# RF_pwr_v2.net
KiCad netlist of a schematic drawn in Altium Designer
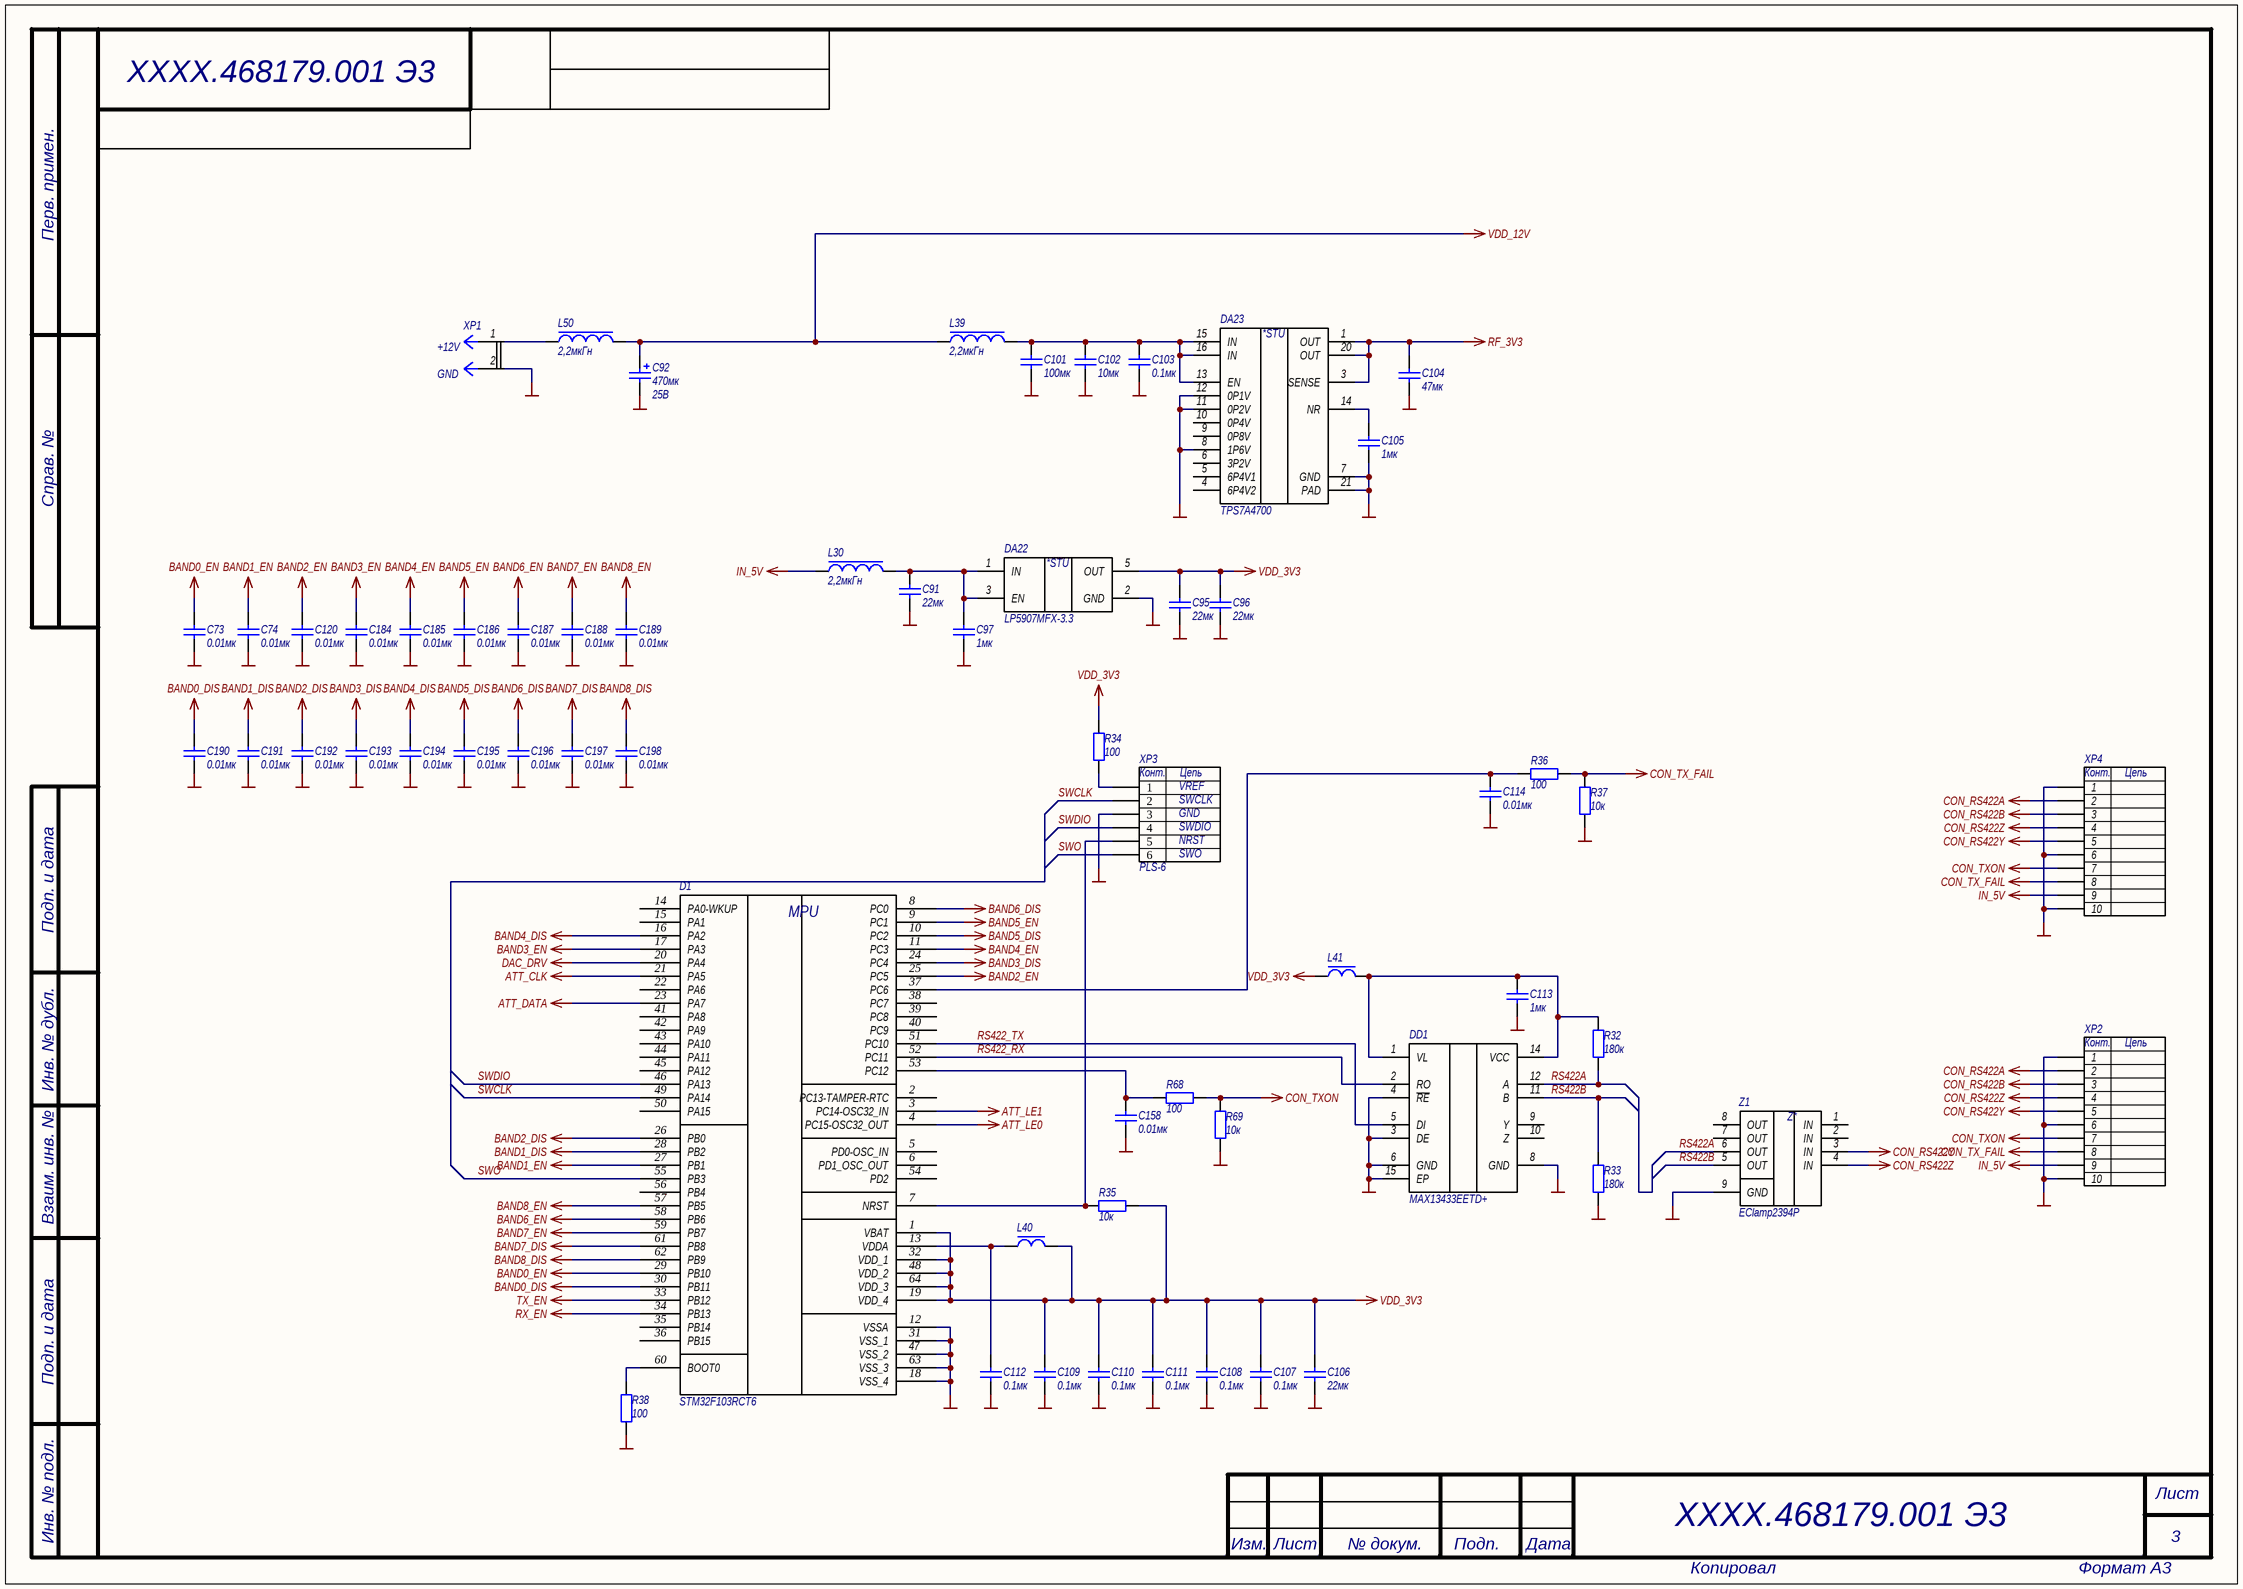
[diagram p0: RF_pwr_v2.SchDoc]

(export (version "E")
  (design (tool "Eeschema 10.0.6"))
  (components
    (comp (ref "C73")
      (value "0.01мк")
      (footprint "CAPC1005X06N")
      (description "Кер. ЧИП-конденсатор")
      (fields (field (name "TOLERANCE") "±20%"))
      (libsource (lib "nels_caps") (part "Кер.ЧИП конд. 0402 0.01мкФ X7R 10%, 50В"))
    )
    (comp (ref "C74")
      (value "0.01мк")
      (footprint "CAPC1005X06N")
      (description "Кер. ЧИП-конденсатор")
      (fields (field (name "TOLERANCE") "±20%"))
      (libsource (lib "nels_caps") (part "Кер.ЧИП конд. 0402 0.01мкФ X7R 10%, 50В"))
    )
    (comp (ref "C91")
      (value "22мк")
      (footprint "CAPC2012X12L")
      (description "Кер. ЧИП-конденсатор")
      (fields (field (name "MANUFACTURER") "TDK") (field (name "TOLERANCE") "±10%"))
      (libsource (lib "nels_caps") (part "Кер.ЧИП конд. 0805 22мкФ X5R 10% 16В"))
    )
    (comp (ref "C92")
      (value "470мк")
      (footprint "CAPAE116103X105N")
      (description "Гибридный ЧИП-конденсатор")
      (fields
        (field (name "TOLERANCE") "±20%")
        (field (name "MANUFACTURERPARTNUMBER") "EEHZK1E471P")
        (field (name "POWER/VOLTAGE") "25В")
        (field (name "PUBLISHER") "Altium Limited")
      )
      (libsource (lib "nels_caps") (part "Конденсатор гибридный SMD 470мкФ ±20% 25В"))
    )
    (comp (ref "C95")
      (value "22мк")
      (footprint "CAPC2012X12L")
      (description "Кер. ЧИП-конденсатор")
      (fields (field (name "MANUFACTURER") "TDK") (field (name "TOLERANCE") "±10%"))
      (libsource (lib "nels_caps") (part "Кер.ЧИП конд. 0805 22мкФ X5R 10% 16В"))
    )
    (comp (ref "C96")
      (value "22мк")
      (footprint "CAPC2012X12L")
      (description "Кер. ЧИП-конденсатор")
      (fields (field (name "MANUFACTURER") "TDK") (field (name "TOLERANCE") "±10%"))
      (libsource (lib "nels_caps") (part "Кер.ЧИП конд. 0805 22мкФ X5R 10% 16В"))
    )
    (comp (ref "C97")
      (value "1мк")
      (footprint "CAPC1005X06N")
      (description "Кер. ЧИП-конденсатор")
      (fields (field (name "TOLERANCE") "±10%"))
      (libsource (lib "nels_caps") (part "Кер.ЧИП конд. 0402 1мкФ X5R 10%, 10В"))
    )
    (comp (ref "C101")
      (value "100мк")
      (footprint "CAPC3216X19L")
      (description "Кер. ЧИП-конденсатор")
      (fields (field (name "MANUFACTURER") "Murata") (field (name "TOLERANCE") "±20%"))
      (libsource (lib "nels_caps") (part "Кер.ЧИП конд. 1206 100мкФ X5R 20% 6.3В"))
    )
    (comp (ref "C102")
      (value "10мк")
      (footprint "CAPC1608X08L")
      (description "Кер. ЧИП-конденсатор")
      (fields (field (name "MANUFACTURER") "Murata") (field (name "TOLERANCE") "±20%"))
      (libsource (lib "nels_caps") (part "Кер.ЧИП конд. 0603 10мкФ X5R 20% 6.3В"))
    )
    (comp (ref "C103")
      (value "0.1мк")
      (footprint "CAPC1005X06N")
      (description "Кер. ЧИП-конденсатор")
      (fields (field (name "TOLERANCE") "±10%"))
      (libsource (lib "nels") (part "Кер.ЧИП конд. 0402 0.1мкФ X7R 10%, 16В"))
    )
    (comp (ref "C104")
      (value "47мк")
      (footprint "CAPC2012X12L")
      (description "Кер. ЧИП-конденсатор")
      (fields (field (name "MANUFACTURER") "Murata") (field (name "TOLERANCE") "±20%"))
      (libsource (lib "nels_caps") (part "Кер.ЧИП конд. 0805 47мкФ X5R 20% 10В"))
    )
    (comp (ref "C105")
      (value "1мк")
      (footprint "CAPC1005X06N")
      (description "Кер. ЧИП-конденсатор")
      (fields (field (name "TOLERANCE") "±10%"))
      (libsource (lib "nels_caps") (part "Кер.ЧИП конд. 0402 1мкФ X5R 10%, 10В"))
    )
    (comp (ref "C106")
      (value "22мк")
      (footprint "CAPC2012X12L")
      (description "Кер. ЧИП-конденсатор")
      (fields (field (name "MANUFACTURER") "TDK") (field (name "TOLERANCE") "±10%"))
      (libsource (lib "nels_caps") (part "Кер.ЧИП конд. 0805 22мкФ X5R 10% 16В"))
    )
    (comp (ref "C107")
      (value "0.1мк")
      (footprint "CAPC1005X06N")
      (description "Кер. ЧИП-конденсатор")
      (fields (field (name "TOLERANCE") "±10%"))
      (libsource (lib "nels") (part "Кер.ЧИП конд. 0402 0.1мкФ X7R 10%, 16В"))
    )
    (comp (ref "C108")
      (value "0.1мк")
      (footprint "CAPC1005X06N")
      (description "Кер. ЧИП-конденсатор")
      (fields (field (name "TOLERANCE") "±10%"))
      (libsource (lib "nels") (part "Кер.ЧИП конд. 0402 0.1мкФ X7R 10%, 16В"))
    )
    (comp (ref "C109")
      (value "0.1мк")
      (footprint "CAPC1005X06N")
      (description "Кер. ЧИП-конденсатор")
      (fields (field (name "TOLERANCE") "±10%"))
      (libsource (lib "nels") (part "Кер.ЧИП конд. 0402 0.1мкФ X7R 10%, 16В"))
    )
    (comp (ref "C110")
      (value "0.1мк")
      (footprint "CAPC1005X06N")
      (description "Кер. ЧИП-конденсатор")
      (fields (field (name "TOLERANCE") "±10%"))
      (libsource (lib "nels") (part "Кер.ЧИП конд. 0402 0.1мкФ X7R 10%, 16В"))
    )
    (comp (ref "C111")
      (value "0.1мк")
      (footprint "CAPC1005X06N")
      (description "Кер. ЧИП-конденсатор")
      (fields (field (name "TOLERANCE") "±10%"))
      (libsource (lib "nels") (part "Кер.ЧИП конд. 0402 0.1мкФ X7R 10%, 16В"))
    )
    (comp (ref "C112")
      (value "0.1мк")
      (footprint "CAPC1005X06N")
      (description "Кер. ЧИП-конденсатор")
      (fields (field (name "TOLERANCE") "±10%"))
      (libsource (lib "nels") (part "Кер.ЧИП конд. 0402 0.1мкФ X7R 10%, 16В"))
    )
    (comp (ref "C113")
      (value "1мк")
      (footprint "CAPC1005X06N")
      (description "Кер. ЧИП-конденсатор")
      (fields (field (name "TOLERANCE") "±10%"))
      (libsource (lib "nels_caps") (part "Кер.ЧИП конд. 0402 1мкФ X5R 10%, 10В"))
    )
    (comp (ref "C114")
      (value "0.01мк")
      (footprint "CAPC1005X06N")
      (description "Кер. ЧИП-конденсатор")
      (fields (field (name "TOLERANCE") "±20%"))
      (libsource (lib "nels_caps") (part "Кер.ЧИП конд. 0402 0.01мкФ X7R 10%, 50В"))
    )
    (comp (ref "C120")
      (value "0.01мк")
      (footprint "CAPC1005X06N")
      (description "Кер. ЧИП-конденсатор")
      (fields (field (name "TOLERANCE") "±20%"))
      (libsource (lib "nels_caps") (part "Кер.ЧИП конд. 0402 0.01мкФ X7R 10%, 50В"))
    )
    (comp (ref "C158")
      (value "0.01мк")
      (footprint "CAPC1005X06N")
      (description "Кер. ЧИП-конденсатор")
      (fields (field (name "TOLERANCE") "±20%"))
      (libsource (lib "nels_caps") (part "Кер.ЧИП конд. 0402 0.01мкФ X7R 10%, 50В"))
    )
    (comp (ref "C184")
      (value "0.01мк")
      (footprint "CAPC1005X06N")
      (description "Кер. ЧИП-конденсатор")
      (fields (field (name "TOLERANCE") "±20%"))
      (libsource (lib "nels_caps") (part "Кер.ЧИП конд. 0402 0.01мкФ X7R 10%, 50В"))
    )
    (comp (ref "C185")
      (value "0.01мк")
      (footprint "CAPC1005X06N")
      (description "Кер. ЧИП-конденсатор")
      (fields (field (name "TOLERANCE") "±20%"))
      (libsource (lib "nels_caps") (part "Кер.ЧИП конд. 0402 0.01мкФ X7R 10%, 50В"))
    )
    (comp (ref "C186")
      (value "0.01мк")
      (footprint "CAPC1005X06N")
      (description "Кер. ЧИП-конденсатор")
      (fields (field (name "TOLERANCE") "±20%"))
      (libsource (lib "nels_caps") (part "Кер.ЧИП конд. 0402 0.01мкФ X7R 10%, 50В"))
    )
    (comp (ref "C187")
      (value "0.01мк")
      (footprint "CAPC1005X06N")
      (description "Кер. ЧИП-конденсатор")
      (fields (field (name "TOLERANCE") "±20%"))
      (libsource (lib "nels_caps") (part "Кер.ЧИП конд. 0402 0.01мкФ X7R 10%, 50В"))
    )
    (comp (ref "C188")
      (value "0.01мк")
      (footprint "CAPC1005X06N")
      (description "Кер. ЧИП-конденсатор")
      (fields (field (name "TOLERANCE") "±20%"))
      (libsource (lib "nels_caps") (part "Кер.ЧИП конд. 0402 0.01мкФ X7R 10%, 50В"))
    )
    (comp (ref "C189")
      (value "0.01мк")
      (footprint "CAPC1005X06N")
      (description "Кер. ЧИП-конденсатор")
      (fields (field (name "TOLERANCE") "±20%"))
      (libsource (lib "nels_caps") (part "Кер.ЧИП конд. 0402 0.01мкФ X7R 10%, 50В"))
    )
    (comp (ref "C190")
      (value "0.01мк")
      (footprint "CAPC1005X06N")
      (description "Кер. ЧИП-конденсатор")
      (fields (field (name "TOLERANCE") "±20%"))
      (libsource (lib "nels_caps") (part "Кер.ЧИП конд. 0402 0.01мкФ X7R 10%, 50В"))
    )
    (comp (ref "C191")
      (value "0.01мк")
      (footprint "CAPC1005X06N")
      (description "Кер. ЧИП-конденсатор")
      (fields (field (name "TOLERANCE") "±20%"))
      (libsource (lib "nels_caps") (part "Кер.ЧИП конд. 0402 0.01мкФ X7R 10%, 50В"))
    )
    (comp (ref "C192")
      (value "0.01мк")
      (footprint "CAPC1005X06N")
      (description "Кер. ЧИП-конденсатор")
      (fields (field (name "TOLERANCE") "±20%"))
      (libsource (lib "nels_caps") (part "Кер.ЧИП конд. 0402 0.01мкФ X7R 10%, 50В"))
    )
    (comp (ref "C193")
      (value "0.01мк")
      (footprint "CAPC1005X06N")
      (description "Кер. ЧИП-конденсатор")
      (fields (field (name "TOLERANCE") "±20%"))
      (libsource (lib "nels_caps") (part "Кер.ЧИП конд. 0402 0.01мкФ X7R 10%, 50В"))
    )
    (comp (ref "C194")
      (value "0.01мк")
      (footprint "CAPC1005X06N")
      (description "Кер. ЧИП-конденсатор")
      (fields (field (name "TOLERANCE") "±20%"))
      (libsource (lib "nels_caps") (part "Кер.ЧИП конд. 0402 0.01мкФ X7R 10%, 50В"))
    )
    (comp (ref "C195")
      (value "0.01мк")
      (footprint "CAPC1005X06N")
      (description "Кер. ЧИП-конденсатор")
      (fields (field (name "TOLERANCE") "±20%"))
      (libsource (lib "nels_caps") (part "Кер.ЧИП конд. 0402 0.01мкФ X7R 10%, 50В"))
    )
    (comp (ref "C196")
      (value "0.01мк")
      (footprint "CAPC1005X06N")
      (description "Кер. ЧИП-конденсатор")
      (fields (field (name "TOLERANCE") "±20%"))
      (libsource (lib "nels_caps") (part "Кер.ЧИП конд. 0402 0.01мкФ X7R 10%, 50В"))
    )
    (comp (ref "C197")
      (value "0.01мк")
      (footprint "CAPC1005X06N")
      (description "Кер. ЧИП-конденсатор")
      (fields (field (name "TOLERANCE") "±20%"))
      (libsource (lib "nels_caps") (part "Кер.ЧИП конд. 0402 0.01мкФ X7R 10%, 50В"))
    )
    (comp (ref "C198")
      (value "0.01мк")
      (footprint "CAPC1005X06N")
      (description "Кер. ЧИП-конденсатор")
      (fields (field (name "TOLERANCE") "±20%"))
      (libsource (lib "nels_caps") (part "Кер.ЧИП конд. 0402 0.01мкФ X7R 10%, 50В"))
    )
    (comp (ref "D1")
      (value "STM32F103RCT6")
      (footprint "QFP50P1200X1200X160-64N")
      (fields (field (name "MANUFACTURER") "STMicroelectronics"))
      (libsource (lib "nels_chip") (part "Микросхема STM32F103RCT6"))
    )
    (comp (ref "DA22")
      (value "LP5907MFX-3.3")
      (footprint "SOT23-5AM")
      (description "250-mA Ultra-Low-Noise, Low-IQ LDO")
      (fields (field (name "MANUFACTURER") "TI"))
      (libsource (lib "nels_chip") (part "Микросхема LP5907MFX-3.3"))
    )
    (comp (ref "DA23")
      (value "TPS7A4700")
      (footprint "QFN65P500X500X100_HS-21L")
      (description "36-V, 1-A, 4-µVRMS, RF LDO Voltage Regulator")
      (fields (field (name "MANUFACTURER") "TI"))
      (libsource (lib "nels_chip") (part "Микросхема TPS7A4700RGW"))
    )
    (comp (ref "DD1")
      (value "MAX13433EETD+")
      (footprint "SON40P300X80_HS-15L")
      (description "RS-422 Transceivers with Low-Voltage Logic Interface 16M")
      (fields (field (name "MANUFACTURER") "Maxim"))
      (libsource (lib "nels_chip") (part "Микросхема MAX13433EETD+"))
    )
    (comp (ref "L30")
      (value "2,2мкГн")
      (footprint "CSAB0420")
      (description "Molding Power Choke")
      (fields
        (field (name "MANUFACTURER") "Vishay")
        (field (name "MANUFACTURERPARTNUMBER") "IHLP1616ABER1R0M11")
      )
      (libsource (lib "nels_ind") (part "ЧИП индуктивность CSAB0420-2R2M"))
    )
    (comp (ref "L39")
      (value "2,2мкГн")
      (footprint "CSAB0420")
      (description "Molding Power Choke")
      (fields
        (field (name "MANUFACTURER") "Vishay")
        (field (name "MANUFACTURERPARTNUMBER") "IHLP1616ABER1R0M11")
      )
      (libsource (lib "nels_ind") (part "ЧИП индуктивность CSAB0420-2R2M"))
    )
    (comp (ref "L40")
      (value "BLM18PG121SN1D")
      (footprint "INDC1608X08L")
      (description "SMD EMI Suppression Filter EMIFIL")
      (fields (field (name "MANUFACTURER") "Murata"))
      (libsource (lib "nels_ind") (part "ЧИП дроссель 0603 BLM18PG121SN1D"))
    )
    (comp (ref "L41")
      (value "BLM18PG121SN1D")
      (footprint "INDC1608X08L")
      (description "SMD EMI Suppression Filter EMIFIL")
      (fields (field (name "MANUFACTURER") "Murata"))
      (libsource (lib "nels_ind") (part "ЧИП дроссель 0603 BLM18PG121SN1D"))
    )
    (comp (ref "L50")
      (value "2,2мкГн")
      (footprint "CSAB0420")
      (description "Molding Power Choke")
      (fields
        (field (name "MANUFACTURER") "Vishay")
        (field (name "MANUFACTURERPARTNUMBER") "IHLP1616ABER1R0M11")
      )
      (libsource (lib "nels_ind") (part "ЧИП индуктивность CSAB0420-2R2M"))
    )
    (comp (ref "R32")
      (value "180к")
      (footprint "RESC1005X06N")
      (description "ЧИП-резистор")
      (fields (field (name "TOLERANCE") "±5%"))
      (libsource (lib "nels") (part "Чип резистор 0402 180 кОм, 5%"))
    )
    (comp (ref "R33")
      (value "180к")
      (footprint "RESC1005X06N")
      (description "ЧИП-резистор")
      (fields (field (name "TOLERANCE") "±5%"))
      (libsource (lib "nels") (part "Чип резистор 0402 180 кОм, 5%"))
    )
    (comp (ref "R34")
      (value "100")
      (footprint "RESC1005X06N")
      (description "ЧИП-резистор")
      (fields (field (name "TOLERANCE") "±5%"))
      (libsource (lib "") (part "Чип резистор 0402 100 Ом, 5%_1"))
    )
    (comp (ref "R35")
      (value "10к")
      (footprint "RESC1005X06N")
      (description "ЧИП-резистор")
      (fields (field (name "TOLERANCE") "±5%"))
      (libsource (lib "") (part "Чип резистор 0402 10 кОм, 5%_1"))
    )
    (comp (ref "R36")
      (value "100")
      (footprint "RESC1005X06N")
      (description "ЧИП-резистор")
      (fields (field (name "TOLERANCE") "±5%"))
      (libsource (lib "nels_res") (part "Чип резистор 0402 100 Ом, 5%"))
    )
    (comp (ref "R37")
      (value "10к")
      (footprint "RESC1005X06N")
      (description "ЧИП-резистор")
      (fields (field (name "TOLERANCE") "±5%"))
      (libsource (lib "nels_res") (part "Чип резистор 0402 10 кОм, 5%"))
    )
    (comp (ref "R38")
      (value "100")
      (footprint "RESC1005X06N")
      (description "ЧИП-резистор")
      (fields (field (name "TOLERANCE") "±5%"))
      (libsource (lib "") (part "Чип резистор 0402 100 Ом, 5%_1"))
    )
    (comp (ref "R68")
      (value "100")
      (footprint "RESC1005X06N")
      (description "ЧИП-резистор")
      (fields (field (name "TOLERANCE") "±5%"))
      (libsource (lib "nels_res") (part "Чип резистор 0402 100 Ом, 5%"))
    )
    (comp (ref "R69")
      (value "10к")
      (footprint "RESC1005X06N")
      (description "ЧИП-резистор")
      (fields (field (name "TOLERANCE") "±5%"))
      (libsource (lib "nels_res") (part "Чип резистор 0402 10 кОм, 5%"))
    )
    (comp (ref "XP1")
      (value "XT30UPB-M")
      (footprint "XT30UPB-M")
      (description "AMASS XT30UPB-M  5 mm")
      (libsource (lib "nels_conn") (part "Соединитель XT30UPB-M"))
    )
    (comp (ref "XP2")
      (value "FH12-10S-0.5SVA")
      (footprint "FH12-10S-0.5SH")
      (description "0.5mm  Pitch FPC/FFC Connector FH12 Series")
      (fields (field (name "MANUFACTURER") "Hirose"))
      (libsource (lib "nels_conn") (part "Соединитель FH12-10S-0.5SVA"))
    )
    (comp (ref "XP3")
      (value "PLS-6")
      (footprint "HDR1X6")
      (description "Вилка штыревая 2.54мм 1x6 прямая тип1")
      (fields (field (name "PUBLISHER") "Altium Limited"))
      (libsource (lib "nels_conn") (part "Соединитель PLS-6"))
    )
    (comp (ref "XP4")
      (value "FH12-10S-0.5SVA")
      (footprint "FH12-10S-0.5SH")
      (description "0.5mm  Pitch FPC/FFC Connector FH12 Series")
      (fields (field (name "MANUFACTURER") "Hirose"))
      (libsource (lib "nels_conn") (part "Соединитель FH12-10S-0.5SVA"))
    )
    (comp (ref "Z1")
      (value "EClamp2394P")
      (footprint "SON50P160X65_HS-9N")
      (description "ESD/EMI Protection  for Color LCD Interfaces")
      (fields (field (name "MANUFACTURER") "SEMTECH"))
      (libsource (lib "nels_other") (part "Фильтр EMI EClamp2394P"))
    )
  )
  (nets
    (net (code "1") (name "/RS422A") (class "Default")
      (node (ref "DD1") (pin "12") (pinfunction "A_12") (pintype "passive"))
      (node (ref "R32") (pin "1") (pinfunction "1_1") (pintype "passive"))
      (node (ref "Z1") (pin "6") (pinfunction "OUT_6") (pintype "passive"))
    )
    (net (code "2") (name "/RS422B") (class "Default")
      (node (ref "DD1") (pin "11") (pinfunction "B_11") (pintype "passive"))
      (node (ref "R33") (pin "2") (pinfunction "2_2") (pintype "passive"))
      (node (ref "Z1") (pin "5") (pinfunction "OUT_5") (pintype "passive"))
    )
    (net (code "3") (name "/RS422_RX") (class "Default")
      (node (ref "D1") (pin "52") (pinfunction "PC11_52") (pintype "passive"))
      (node (ref "DD1") (pin "2") (pinfunction "RO_2") (pintype "passive"))
    )
    (net (code "4") (name "/RS422_TX") (class "Default")
      (node (ref "D1") (pin "51") (pinfunction "PC10_51") (pintype "passive"))
      (node (ref "DD1") (pin "5") (pinfunction "DI_5") (pintype "passive"))
    )
    (net (code "5") (name "/SWCLK") (class "Default")
      (node (ref "D1") (pin "49") (pinfunction "PA14_49") (pintype "passive"))
      (node (ref "XP3") (pin "2") (pinfunction "2_2") (pintype "passive"))
    )
    (net (code "6") (name "/SWDIO") (class "Default")
      (node (ref "D1") (pin "46") (pinfunction "PA13_46") (pintype "passive"))
      (node (ref "XP3") (pin "4") (pinfunction "4_4") (pintype "passive"))
    )
    (net (code "7") (name "/SWO") (class "Default")
      (node (ref "D1") (pin "55") (pinfunction "PB3_55") (pintype "passive"))
      (node (ref "XP3") (pin "6") (pinfunction "6_6") (pintype "passive"))
    )
    (net (code "8") (name "ATT_CLK") (class "Default")
      (node (ref "D1") (pin "21") (pinfunction "PA5_21") (pintype "passive"))
    )
    (net (code "9") (name "ATT_DATA") (class "Default")
      (node (ref "D1") (pin "23") (pinfunction "PA7_23") (pintype "passive"))
    )
    (net (code "10") (name "ATT_LE0") (class "Default")
      (node (ref "D1") (pin "4") (pinfunction "PC15-OSC32_OUT_4") (pintype "passive"))
    )
    (net (code "11") (name "ATT_LE1") (class "Default")
      (node (ref "D1") (pin "3") (pinfunction "PC14-OSC32_IN_3") (pintype "passive"))
    )
    (net (code "12") (name "BAND0_DIS") (class "Default")
      (node (ref "C190") (pin "2") (pinfunction "2_2") (pintype "passive"))
      (node (ref "D1") (pin "30") (pinfunction "PB11_30") (pintype "passive"))
    )
    (net (code "13") (name "BAND0_EN") (class "Default")
      (node (ref "C73") (pin "2") (pinfunction "2_2") (pintype "passive"))
      (node (ref "D1") (pin "29") (pinfunction "PB10_29") (pintype "passive"))
    )
    (net (code "14") (name "BAND1_DIS") (class "Default")
      (node (ref "C191") (pin "2") (pinfunction "2_2") (pintype "passive"))
      (node (ref "D1") (pin "28") (pinfunction "PB2_28") (pintype "passive"))
    )
    (net (code "15") (name "BAND1_EN") (class "Default")
      (node (ref "C74") (pin "2") (pinfunction "2_2") (pintype "passive"))
      (node (ref "D1") (pin "27") (pinfunction "PB1_27") (pintype "passive"))
    )
    (net (code "16") (name "BAND2_DIS") (class "Default")
      (node (ref "C192") (pin "2") (pinfunction "2_2") (pintype "passive"))
      (node (ref "D1") (pin "26") (pinfunction "PB0_26") (pintype "passive"))
    )
    (net (code "17") (name "BAND2_EN") (class "Default")
      (node (ref "C120") (pin "2") (pinfunction "2_2") (pintype "passive"))
      (node (ref "D1") (pin "25") (pinfunction "PC5_25") (pintype "passive"))
    )
    (net (code "18") (name "BAND3_DIS") (class "Default")
      (node (ref "C193") (pin "2") (pinfunction "2_2") (pintype "passive"))
      (node (ref "D1") (pin "24") (pinfunction "PC4_24") (pintype "passive"))
    )
    (net (code "19") (name "BAND3_EN") (class "Default")
      (node (ref "C184") (pin "2") (pinfunction "2_2") (pintype "passive"))
      (node (ref "D1") (pin "17") (pinfunction "PA3_17") (pintype "passive"))
    )
    (net (code "20") (name "BAND4_DIS") (class "Default")
      (node (ref "C194") (pin "2") (pinfunction "2_2") (pintype "passive"))
      (node (ref "D1") (pin "16") (pinfunction "PA2_16") (pintype "passive"))
    )
    (net (code "21") (name "BAND4_EN") (class "Default")
      (node (ref "C185") (pin "2") (pinfunction "2_2") (pintype "passive"))
      (node (ref "D1") (pin "11") (pinfunction "PC3_11") (pintype "passive"))
    )
    (net (code "22") (name "BAND5_DIS") (class "Default")
      (node (ref "C195") (pin "2") (pinfunction "2_2") (pintype "passive"))
      (node (ref "D1") (pin "10") (pinfunction "PC2_10") (pintype "passive"))
    )
    (net (code "23") (name "BAND5_EN") (class "Default")
      (node (ref "C186") (pin "2") (pinfunction "2_2") (pintype "passive"))
      (node (ref "D1") (pin "9") (pinfunction "PC1_9") (pintype "passive"))
    )
    (net (code "24") (name "BAND6_DIS") (class "Default")
      (node (ref "C196") (pin "2") (pinfunction "2_2") (pintype "passive"))
      (node (ref "D1") (pin "8") (pinfunction "PC0_8") (pintype "passive"))
    )
    (net (code "25") (name "BAND6_EN") (class "Default")
      (node (ref "C187") (pin "2") (pinfunction "2_2") (pintype "passive"))
      (node (ref "D1") (pin "58") (pinfunction "PB6_58") (pintype "passive"))
    )
    (net (code "26") (name "BAND7_DIS") (class "Default")
      (node (ref "C197") (pin "2") (pinfunction "2_2") (pintype "passive"))
      (node (ref "D1") (pin "61") (pinfunction "PB8_61") (pintype "passive"))
    )
    (net (code "27") (name "BAND7_EN") (class "Default")
      (node (ref "C188") (pin "2") (pinfunction "2_2") (pintype "passive"))
      (node (ref "D1") (pin "59") (pinfunction "PB7_59") (pintype "passive"))
    )
    (net (code "28") (name "BAND8_DIS") (class "Default")
      (node (ref "C198") (pin "2") (pinfunction "2_2") (pintype "passive"))
      (node (ref "D1") (pin "62") (pinfunction "PB9_62") (pintype "passive"))
    )
    (net (code "29") (name "BAND8_EN") (class "Default")
      (node (ref "C189") (pin "2") (pinfunction "2_2") (pintype "passive"))
      (node (ref "D1") (pin "57") (pinfunction "PB5_57") (pintype "passive"))
    )
    (net (code "30") (name "CON_RS422A") (class "Default")
      (node (ref "XP2") (pin "2") (pinfunction "2_2") (pintype "passive"))
      (node (ref "XP4") (pin "2") (pinfunction "2_2") (pintype "passive"))
    )
    (net (code "31") (name "CON_RS422B") (class "Default")
      (node (ref "XP2") (pin "3") (pinfunction "3_3") (pintype "passive"))
      (node (ref "XP4") (pin "3") (pinfunction "3_3") (pintype "passive"))
    )
    (net (code "32") (name "CON_RS422Y") (class "Default")
      (node (ref "XP2") (pin "5") (pinfunction "5_5") (pintype "passive"))
      (node (ref "XP4") (pin "5") (pinfunction "5_5") (pintype "passive"))
      (node (ref "Z1") (pin "3") (pinfunction "IN_3") (pintype "passive"))
    )
    (net (code "33") (name "CON_RS422Z") (class "Default")
      (node (ref "XP2") (pin "4") (pinfunction "4_4") (pintype "passive"))
      (node (ref "XP4") (pin "4") (pinfunction "4_4") (pintype "passive"))
      (node (ref "Z1") (pin "4") (pinfunction "IN_4") (pintype "passive"))
    )
    (net (code "34") (name "CON_TXON") (class "Default")
      (node (ref "R68") (pin "1") (pinfunction "1_1") (pintype "passive"))
      (node (ref "R69") (pin "1") (pinfunction "1_1") (pintype "passive"))
      (node (ref "XP2") (pin "7") (pinfunction "7_7") (pintype "passive"))
      (node (ref "XP4") (pin "7") (pinfunction "7_7") (pintype "passive"))
    )
    (net (code "35") (name "CON_TX_FAIL") (class "Default")
      (node (ref "R36") (pin "1") (pinfunction "1_1") (pintype "passive"))
      (node (ref "R37") (pin "1") (pinfunction "1_1") (pintype "passive"))
      (node (ref "XP2") (pin "8") (pinfunction "8_8") (pintype "passive"))
      (node (ref "XP4") (pin "8") (pinfunction "8_8") (pintype "passive"))
    )
    (net (code "36") (name "DAC_DRV") (class "Default")
      (node (ref "D1") (pin "20") (pinfunction "PA4_20") (pintype "passive"))
    )
    (net (code "37") (name "GND") (class "Default")
      (node (ref "C101") (pin "1") (pinfunction "1_1") (pintype "passive"))
      (node (ref "C102") (pin "1") (pinfunction "1_1") (pintype "passive"))
      (node (ref "C103") (pin "1") (pinfunction "1_1") (pintype "passive"))
      (node (ref "C104") (pin "1") (pinfunction "1_1") (pintype "passive"))
      (node (ref "C105") (pin "1") (pinfunction "1_1") (pintype "passive"))
      (node (ref "C106") (pin "1") (pinfunction "1_1") (pintype "passive"))
      (node (ref "C107") (pin "1") (pinfunction "1_1") (pintype "passive"))
      (node (ref "C108") (pin "1") (pinfunction "1_1") (pintype "passive"))
      (node (ref "C109") (pin "1") (pinfunction "1_1") (pintype "passive"))
      (node (ref "C110") (pin "1") (pinfunction "1_1") (pintype "passive"))
      (node (ref "C111") (pin "1") (pinfunction "1_1") (pintype "passive"))
      (node (ref "C112") (pin "1") (pinfunction "1_1") (pintype "passive"))
      (node (ref "C113") (pin "1") (pinfunction "1_1") (pintype "passive"))
      (node (ref "C114") (pin "1") (pinfunction "1_1") (pintype "passive"))
      (node (ref "C120") (pin "1") (pinfunction "1_1") (pintype "passive"))
      (node (ref "C158") (pin "1") (pinfunction "1_1") (pintype "passive"))
      (node (ref "C184") (pin "1") (pinfunction "1_1") (pintype "passive"))
      (node (ref "C185") (pin "1") (pinfunction "1_1") (pintype "passive"))
      (node (ref "C186") (pin "1") (pinfunction "1_1") (pintype "passive"))
      (node (ref "C187") (pin "1") (pinfunction "1_1") (pintype "passive"))
      (node (ref "C188") (pin "1") (pinfunction "1_1") (pintype "passive"))
      (node (ref "C189") (pin "1") (pinfunction "1_1") (pintype "passive"))
      (node (ref "C190") (pin "1") (pinfunction "1_1") (pintype "passive"))
      (node (ref "C191") (pin "1") (pinfunction "1_1") (pintype "passive"))
      (node (ref "C192") (pin "1") (pinfunction "1_1") (pintype "passive"))
      (node (ref "C193") (pin "1") (pinfunction "1_1") (pintype "passive"))
      (node (ref "C194") (pin "1") (pinfunction "1_1") (pintype "passive"))
      (node (ref "C195") (pin "1") (pinfunction "1_1") (pintype "passive"))
      (node (ref "C196") (pin "1") (pinfunction "1_1") (pintype "passive"))
      (node (ref "C197") (pin "1") (pinfunction "1_1") (pintype "passive"))
      (node (ref "C198") (pin "1") (pinfunction "1_1") (pintype "passive"))
      (node (ref "C73") (pin "1") (pinfunction "1_1") (pintype "passive"))
      (node (ref "C74") (pin "1") (pinfunction "1_1") (pintype "passive"))
      (node (ref "C91") (pin "1") (pinfunction "1_1") (pintype "passive"))
      (node (ref "C92") (pin "2") (pinfunction "2_2") (pintype "passive"))
      (node (ref "C95") (pin "1") (pinfunction "1_1") (pintype "passive"))
      (node (ref "C96") (pin "1") (pinfunction "1_1") (pintype "passive"))
      (node (ref "C97") (pin "1") (pinfunction "1_1") (pintype "passive"))
      (node (ref "D1") (pin "12") (pinfunction "VSSA_12") (pintype "passive"))
      (node (ref "D1") (pin "18") (pinfunction "VSS_4_18") (pintype "passive"))
      (node (ref "D1") (pin "31") (pinfunction "VSS_1_31") (pintype "passive"))
      (node (ref "D1") (pin "47") (pinfunction "VSS_2_47") (pintype "passive"))
      (node (ref "D1") (pin "63") (pinfunction "VSS_3_63") (pintype "passive"))
      (node (ref "DA22") (pin "2") (pinfunction "GND_2") (pintype "passive"))
      (node (ref "DA23") (pin "11") (pinfunction "0P2V_11") (pintype "passive"))
      (node (ref "DA23") (pin "12") (pinfunction "0P1V_12") (pintype "passive"))
      (node (ref "DA23") (pin "21") (pinfunction "PAD_21") (pintype "passive"))
      (node (ref "DA23") (pin "7") (pinfunction "GND_7") (pintype "passive"))
      (node (ref "DA23") (pin "8") (pinfunction "1P6V_8") (pintype "passive"))
      (node (ref "DD1") (pin "15") (pinfunction "EP_15") (pintype "passive"))
      (node (ref "DD1") (pin "3") (pinfunction "DE_3") (pintype "passive"))
      (node (ref "DD1") (pin "4") (pinfunction "~{RE}_4") (pintype "passive"))
      (node (ref "DD1") (pin "6") (pinfunction "GND_6") (pintype "passive"))
      (node (ref "DD1") (pin "8") (pinfunction "GND_8") (pintype "passive"))
      (node (ref "R33") (pin "1") (pinfunction "1_1") (pintype "passive"))
      (node (ref "R37") (pin "2") (pinfunction "2_2") (pintype "passive"))
      (node (ref "R38") (pin "2") (pinfunction "2_2") (pintype "passive"))
      (node (ref "R69") (pin "2") (pinfunction "2_2") (pintype "passive"))
      (node (ref "XP1") (pin "2") (pinfunction "~_2") (pintype "passive"))
      (node (ref "XP2") (pin "1") (pinfunction "1_1") (pintype "passive"))
      (node (ref "XP2") (pin "10") (pinfunction "10_10") (pintype "passive"))
      (node (ref "XP2") (pin "6") (pinfunction "6_6") (pintype "passive"))
      (node (ref "XP3") (pin "3") (pinfunction "3_3") (pintype "passive"))
      (node (ref "XP4") (pin "1") (pinfunction "1_1") (pintype "passive"))
      (node (ref "XP4") (pin "10") (pinfunction "10_10") (pintype "passive"))
      (node (ref "XP4") (pin "6") (pinfunction "6_6") (pintype "passive"))
      (node (ref "Z1") (pin "9") (pinfunction "GND_9") (pintype "passive"))
    )
    (net (code "38") (name "IN_5V") (class "Default")
      (node (ref "L30") (pin "1") (pinfunction "1_1") (pintype "passive"))
      (node (ref "XP2") (pin "9") (pinfunction "9_9") (pintype "passive"))
      (node (ref "XP4") (pin "9") (pinfunction "9_9") (pintype "passive"))
    )
    (net (code "39") (name "Net-(D1-BOOT0)") (class "Default")
      (node (ref "D1") (pin "60") (pinfunction "BOOT0_60") (pintype "passive"))
      (node (ref "R38") (pin "1") (pinfunction "1_1") (pintype "passive"))
    )
    (net (code "40") (name "Net-(D1-NRST)") (class "Default")
      (node (ref "D1") (pin "7") (pinfunction "NRST_7") (pintype "passive"))
      (node (ref "R35") (pin "1") (pinfunction "1_1") (pintype "passive"))
      (node (ref "XP3") (pin "5") (pinfunction "5_5") (pintype "passive"))
    )
    (net (code "41") (name "Net-(D1-PC6)") (class "Default")
      (node (ref "C114") (pin "2") (pinfunction "2_2") (pintype "passive"))
      (node (ref "D1") (pin "37") (pinfunction "PC6_37") (pintype "passive"))
      (node (ref "R36") (pin "2") (pinfunction "2_2") (pintype "passive"))
    )
    (net (code "42") (name "Net-(D1-PC12)") (class "Default")
      (node (ref "C158") (pin "2") (pinfunction "2_2") (pintype "passive"))
      (node (ref "D1") (pin "53") (pinfunction "PC12_53") (pintype "passive"))
      (node (ref "R68") (pin "2") (pinfunction "2_2") (pintype "passive"))
    )
    (net (code "43") (name "Net-(D1-VDDA)") (class "Default")
      (node (ref "C112") (pin "2") (pinfunction "2_2") (pintype "passive"))
      (node (ref "D1") (pin "13") (pinfunction "VDDA_13") (pintype "passive"))
      (node (ref "L40") (pin "1") (pinfunction "1_1") (pintype "passive"))
    )
    (net (code "44") (name "Net-(DA22-EN)") (class "Default")
      (node (ref "C91") (pin "2") (pinfunction "2_2") (pintype "passive"))
      (node (ref "C97") (pin "2") (pinfunction "2_2") (pintype "passive"))
      (node (ref "DA22") (pin "1") (pinfunction "IN_1") (pintype "passive"))
      (node (ref "DA22") (pin "3") (pinfunction "EN_3") (pintype "passive"))
      (node (ref "L30") (pin "2") (pinfunction "2_2") (pintype "passive"))
    )
    (net (code "45") (name "Net-(DA23-EN)") (class "Default")
      (node (ref "C101") (pin "2") (pinfunction "2_2") (pintype "passive"))
      (node (ref "C102") (pin "2") (pinfunction "2_2") (pintype "passive"))
      (node (ref "C103") (pin "2") (pinfunction "2_2") (pintype "passive"))
      (node (ref "DA23") (pin "13") (pinfunction "EN_13") (pintype "passive"))
      (node (ref "DA23") (pin "15") (pinfunction "IN_15") (pintype "passive"))
      (node (ref "DA23") (pin "16") (pinfunction "IN_16") (pintype "passive"))
      (node (ref "L39") (pin "2") (pinfunction "2_2") (pintype "passive"))
    )
    (net (code "46") (name "Net-(DA23-NR)") (class "Default")
      (node (ref "C105") (pin "2") (pinfunction "2_2") (pintype "passive"))
      (node (ref "DA23") (pin "14") (pinfunction "NR_14") (pintype "passive"))
    )
    (net (code "47") (name "Net-(DD1-VCC)") (class "Default")
      (node (ref "C113") (pin "2") (pinfunction "2_2") (pintype "passive"))
      (node (ref "DD1") (pin "1") (pinfunction "VL_1") (pintype "passive"))
      (node (ref "DD1") (pin "14") (pinfunction "VCC_14") (pintype "passive"))
      (node (ref "L41") (pin "2") (pinfunction "2_2") (pintype "passive"))
      (node (ref "R32") (pin "2") (pinfunction "2_2") (pintype "passive"))
    )
    (net (code "48") (name "Net-(L50-Pad1)") (class "Default")
      (node (ref "L50") (pin "1") (pinfunction "1_1") (pintype "passive"))
      (node (ref "XP1") (pin "1") (pinfunction "~_1") (pintype "passive"))
    )
    (net (code "49") (name "Net-(R34-Pad2)") (class "Default")
      (node (ref "R34") (pin "2") (pinfunction "2_2") (pintype "passive"))
      (node (ref "XP3") (pin "1") (pinfunction "1_1") (pintype "passive"))
    )
    (net (code "50") (name "RF_3V3") (class "Default")
      (node (ref "C104") (pin "2") (pinfunction "2_2") (pintype "passive"))
      (node (ref "DA23") (pin "1") (pinfunction "OUT_1") (pintype "passive"))
      (node (ref "DA23") (pin "20") (pinfunction "OUT_20") (pintype "passive"))
      (node (ref "DA23") (pin "3") (pinfunction "SENSE_3") (pintype "passive"))
    )
    (net (code "51") (name "RX_EN") (class "Default")
      (node (ref "D1") (pin "34") (pinfunction "PB13_34") (pintype "passive"))
    )
    (net (code "52") (name "TX_EN") (class "Default")
      (node (ref "D1") (pin "33") (pinfunction "PB12_33") (pintype "passive"))
    )
    (net (code "53") (name "VDD_3V3") (class "Default")
      (node (ref "C106") (pin "2") (pinfunction "2_2") (pintype "passive"))
      (node (ref "C107") (pin "2") (pinfunction "2_2") (pintype "passive"))
      (node (ref "C108") (pin "2") (pinfunction "2_2") (pintype "passive"))
      (node (ref "C109") (pin "2") (pinfunction "2_2") (pintype "passive"))
      (node (ref "C110") (pin "2") (pinfunction "2_2") (pintype "passive"))
      (node (ref "C111") (pin "2") (pinfunction "2_2") (pintype "passive"))
      (node (ref "C95") (pin "2") (pinfunction "2_2") (pintype "passive"))
      (node (ref "C96") (pin "2") (pinfunction "2_2") (pintype "passive"))
      (node (ref "D1") (pin "1") (pinfunction "VBAT_1") (pintype "passive"))
      (node (ref "D1") (pin "19") (pinfunction "VDD_4_19") (pintype "passive"))
      (node (ref "D1") (pin "32") (pinfunction "VDD_1_32") (pintype "passive"))
      (node (ref "D1") (pin "48") (pinfunction "VDD_2_48") (pintype "passive"))
      (node (ref "D1") (pin "64") (pinfunction "VDD_3_64") (pintype "passive"))
      (node (ref "DA22") (pin "5") (pinfunction "OUT_5") (pintype "passive"))
      (node (ref "L40") (pin "2") (pinfunction "2_2") (pintype "passive"))
      (node (ref "L41") (pin "1") (pinfunction "1_1") (pintype "passive"))
      (node (ref "R34") (pin "1") (pinfunction "1_1") (pintype "passive"))
      (node (ref "R35") (pin "2") (pinfunction "2_2") (pintype "passive"))
    )
    (net (code "54") (name "VDD_12V") (class "Default")
      (node (ref "C92") (pin "1") (pinfunction "1_1") (pintype "passive"))
      (node (ref "L39") (pin "1") (pinfunction "1_1") (pintype "passive"))
      (node (ref "L50") (pin "2") (pinfunction "2_2") (pintype "passive"))
    )
    (net (code "55") (name "unconnected-(D1-PA0-WKUP-Pad14)") (class "Default")
      (node (ref "D1") (pin "14") (pinfunction "PA0-WKUP_14") (pintype "passive"))
    )
    (net (code "56") (name "unconnected-(D1-PA1-Pad15)") (class "Default")
      (node (ref "D1") (pin "15") (pinfunction "PA1_15") (pintype "passive"))
    )
    (net (code "57") (name "unconnected-(D1-PA6-Pad22)") (class "Default")
      (node (ref "D1") (pin "22") (pinfunction "PA6_22") (pintype "passive"))
    )
    (net (code "58") (name "unconnected-(D1-PA8-Pad41)") (class "Default")
      (node (ref "D1") (pin "41") (pinfunction "PA8_41") (pintype "passive"))
    )
    (net (code "59") (name "unconnected-(D1-PA9-Pad42)") (class "Default")
      (node (ref "D1") (pin "42") (pinfunction "PA9_42") (pintype "passive"))
    )
    (net (code "60") (name "unconnected-(D1-PA10-Pad43)") (class "Default")
      (node (ref "D1") (pin "43") (pinfunction "PA10_43") (pintype "passive"))
    )
    (net (code "61") (name "unconnected-(D1-PA11-Pad44)") (class "Default")
      (node (ref "D1") (pin "44") (pinfunction "PA11_44") (pintype "passive"))
    )
    (net (code "62") (name "unconnected-(D1-PA12-Pad45)") (class "Default")
      (node (ref "D1") (pin "45") (pinfunction "PA12_45") (pintype "passive"))
    )
    (net (code "63") (name "unconnected-(D1-PA15-Pad50)") (class "Default")
      (node (ref "D1") (pin "50") (pinfunction "PA15_50") (pintype "passive"))
    )
    (net (code "64") (name "unconnected-(D1-PB4-Pad56)") (class "Default")
      (node (ref "D1") (pin "56") (pinfunction "PB4_56") (pintype "passive"))
    )
    (net (code "65") (name "unconnected-(D1-PB14-Pad35)") (class "Default")
      (node (ref "D1") (pin "35") (pinfunction "PB14_35") (pintype "passive"))
    )
    (net (code "66") (name "unconnected-(D1-PB15-Pad36)") (class "Default")
      (node (ref "D1") (pin "36") (pinfunction "PB15_36") (pintype "passive"))
    )
    (net (code "67") (name "unconnected-(D1-PC7-Pad38)") (class "Default")
      (node (ref "D1") (pin "38") (pinfunction "PC7_38") (pintype "passive"))
    )
    (net (code "68") (name "unconnected-(D1-PC8-Pad39)") (class "Default")
      (node (ref "D1") (pin "39") (pinfunction "PC8_39") (pintype "passive"))
    )
    (net (code "69") (name "unconnected-(D1-PC9-Pad40)") (class "Default")
      (node (ref "D1") (pin "40") (pinfunction "PC9_40") (pintype "passive"))
    )
    (net (code "70") (name "unconnected-(D1-PC13-TAMPER-RTC-Pad2)") (class "Default")
      (node (ref "D1") (pin "2") (pinfunction "PC13-TAMPER-RTC_2") (pintype "passive"))
    )
    (net (code "71") (name "unconnected-(D1-PD0-OSC_IN-Pad5)") (class "Default")
      (node (ref "D1") (pin "5") (pinfunction "PD0-OSC_IN_5") (pintype "passive"))
    )
    (net (code "72") (name "unconnected-(D1-PD1_OSC_OUT-Pad6)") (class "Default")
      (node (ref "D1") (pin "6") (pinfunction "PD1_OSC_OUT_6") (pintype "passive"))
    )
    (net (code "73") (name "unconnected-(D1-PD2-Pad54)") (class "Default")
      (node (ref "D1") (pin "54") (pinfunction "PD2_54") (pintype "passive"))
    )
    (net (code "74") (name "unconnected-(DA23-0P4V-Pad10)") (class "Default")
      (node (ref "DA23") (pin "10") (pinfunction "0P4V_10") (pintype "passive"))
    )
    (net (code "75") (name "unconnected-(DA23-0P8V-Pad9)") (class "Default")
      (node (ref "DA23") (pin "9") (pinfunction "0P8V_9") (pintype "passive"))
    )
    (net (code "76") (name "unconnected-(DA23-3P2V-Pad6)") (class "Default")
      (node (ref "DA23") (pin "6") (pinfunction "3P2V_6") (pintype "passive"))
    )
    (net (code "77") (name "unconnected-(DA23-6P4V1-Pad5)") (class "Default")
      (node (ref "DA23") (pin "5") (pinfunction "6P4V1_5") (pintype "passive"))
    )
    (net (code "78") (name "unconnected-(DA23-6P4V2-Pad4)") (class "Default")
      (node (ref "DA23") (pin "4") (pinfunction "6P4V2_4") (pintype "passive"))
    )
    (net (code "79") (name "unconnected-(DD1-Y-Pad9)") (class "Default")
      (node (ref "DD1") (pin "9") (pinfunction "Y_9") (pintype "passive"))
    )
    (net (code "80") (name "unconnected-(DD1-Z-Pad10)") (class "Default")
      (node (ref "DD1") (pin "10") (pinfunction "Z_10") (pintype "passive"))
    )
    (net (code "81") (name "unconnected-(Z1-IN-Pad1)") (class "Default")
      (node (ref "Z1") (pin "1") (pinfunction "IN_1") (pintype "passive"))
    )
    (net (code "82") (name "unconnected-(Z1-IN-Pad2)") (class "Default")
      (node (ref "Z1") (pin "2") (pinfunction "IN_2") (pintype "passive"))
    )
    (net (code "83") (name "unconnected-(Z1-OUT-Pad7)") (class "Default")
      (node (ref "Z1") (pin "7") (pinfunction "OUT_7") (pintype "passive"))
    )
    (net (code "84") (name "unconnected-(Z1-OUT-Pad8)") (class "Default")
      (node (ref "Z1") (pin "8") (pinfunction "OUT_8") (pintype "passive"))
    )
  )
)
